# ESP32_Relay_Mainboard.net
KiCad netlist of a schematic drawn in EAGLE
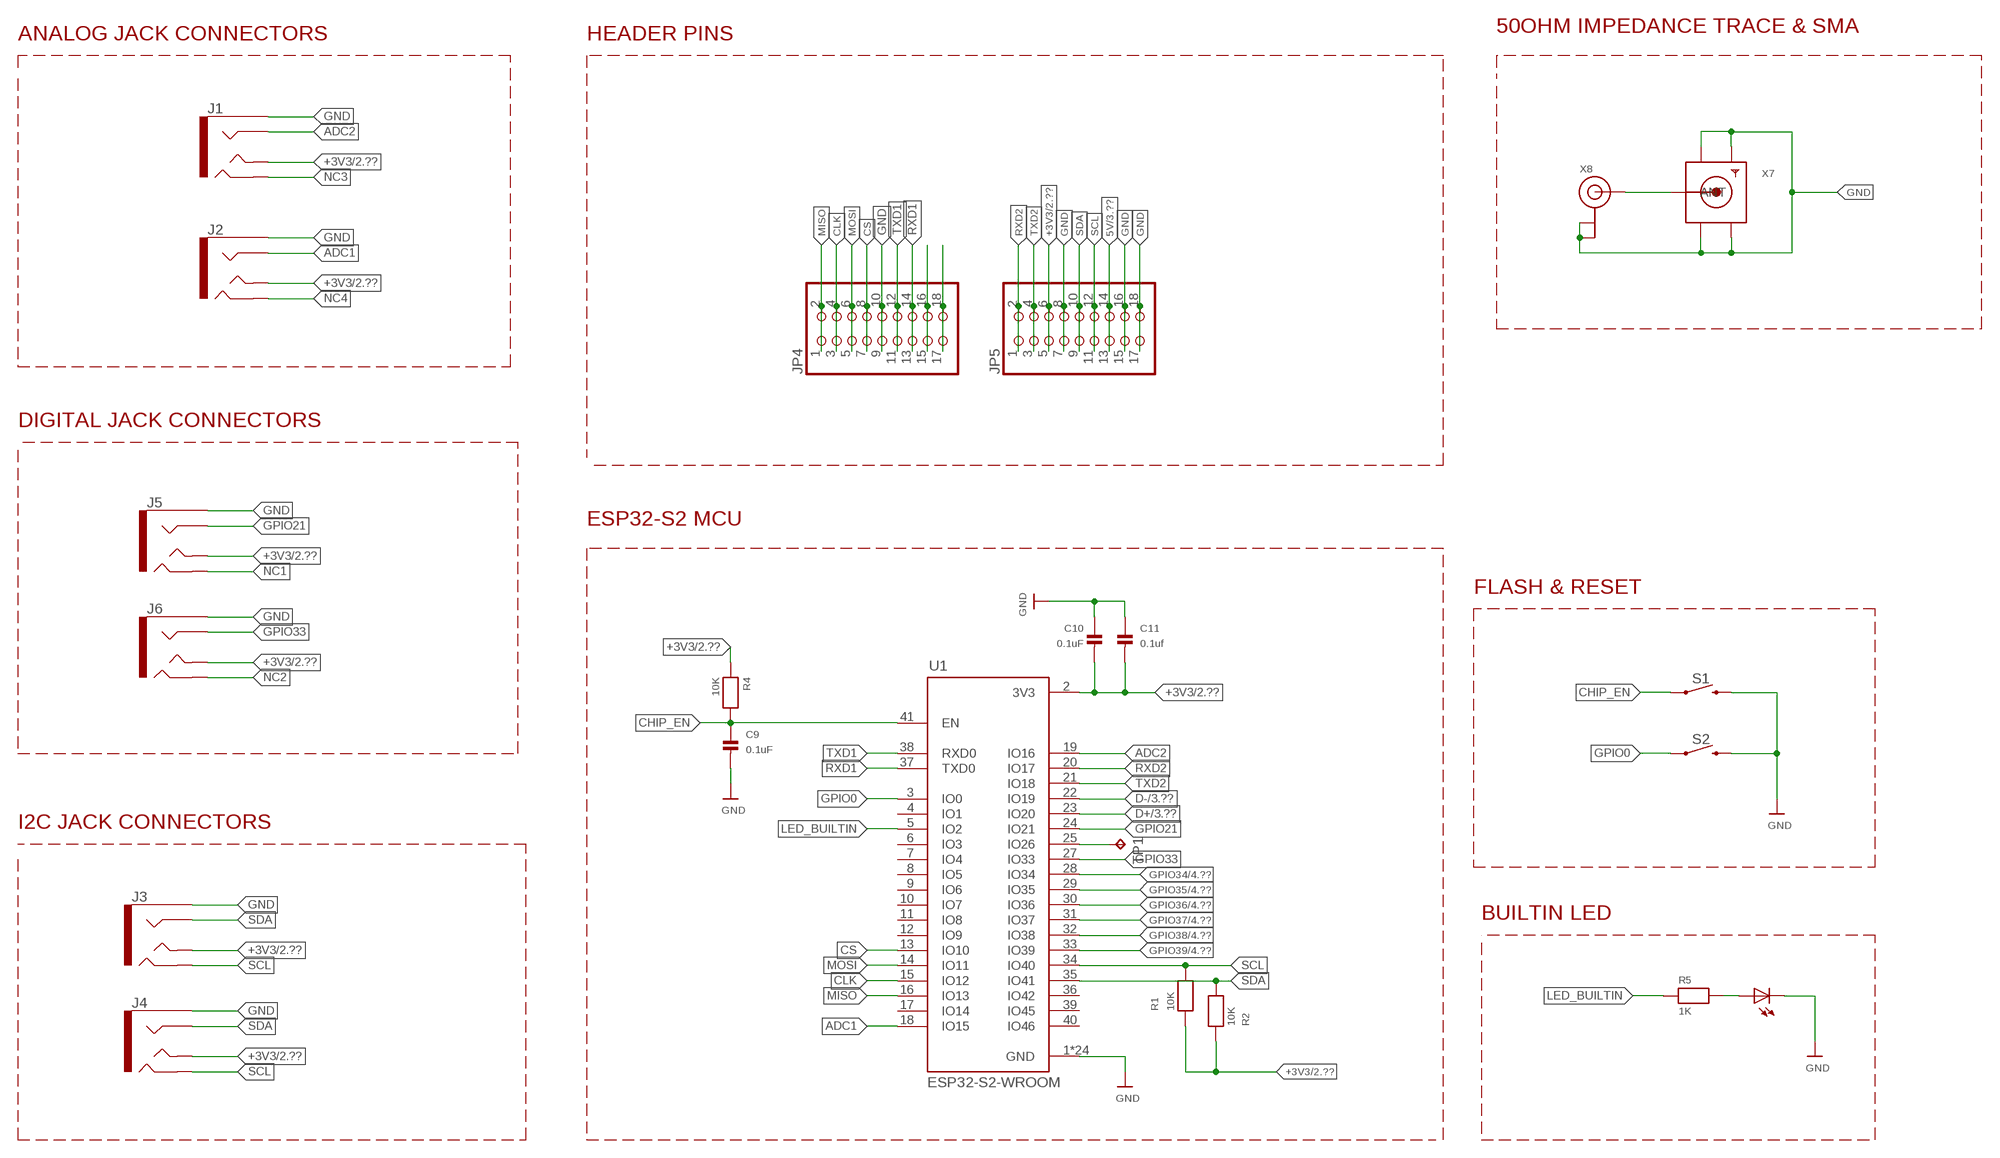
[diagram p0: schematic, sheet 1]
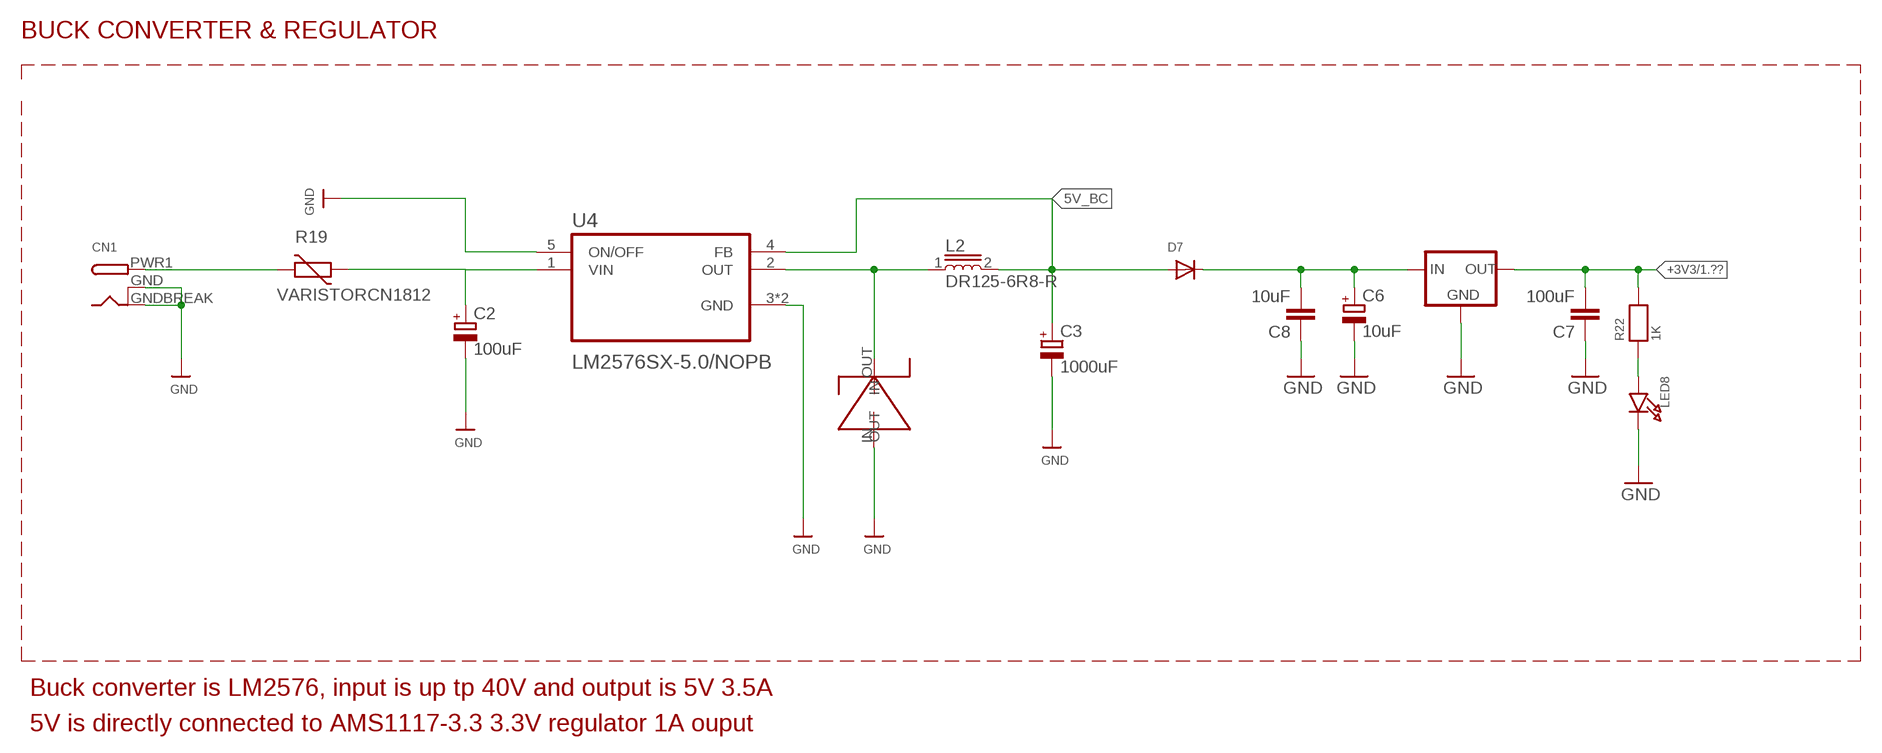
[diagram p1: schematic, sheet 2]
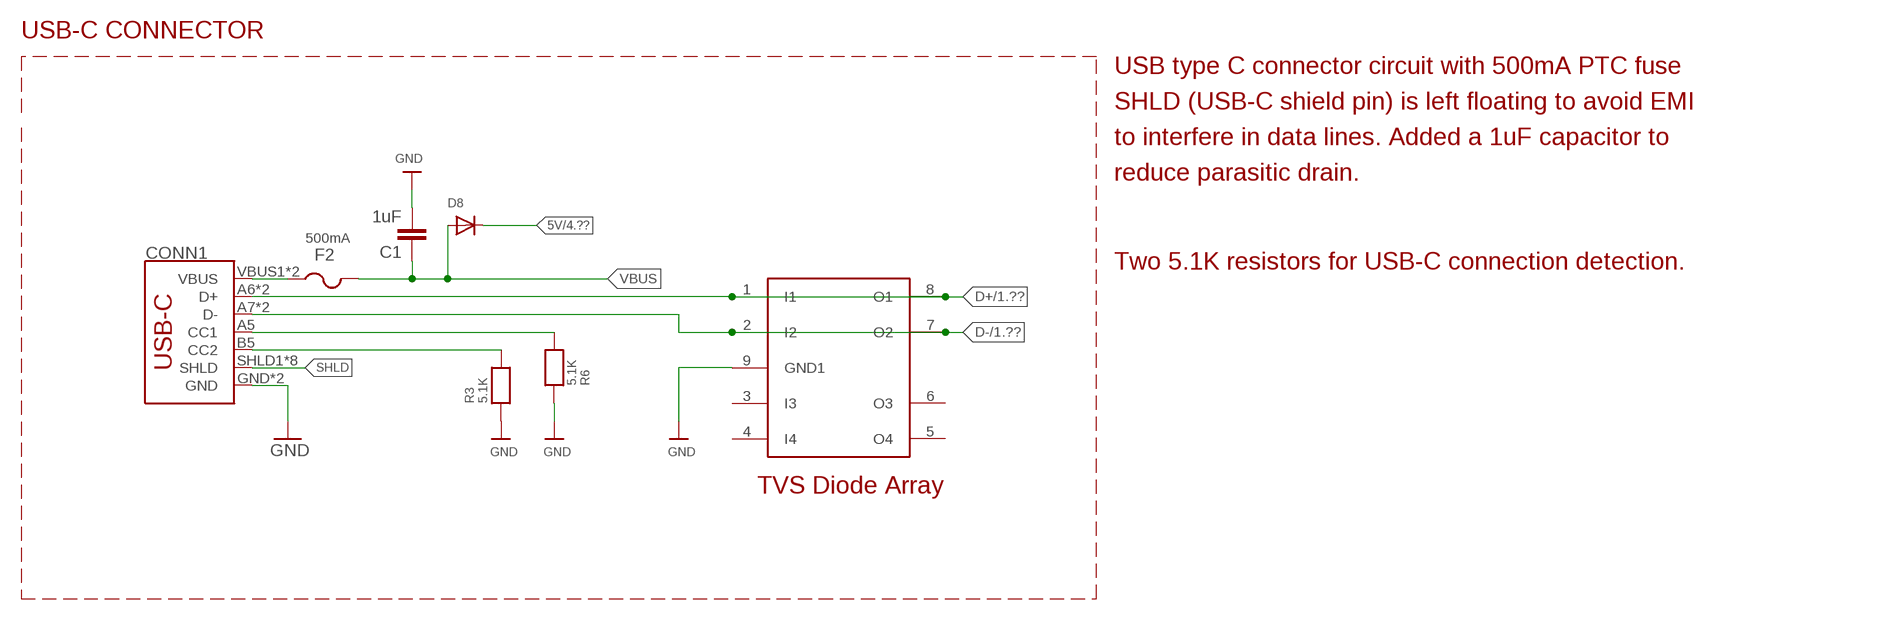
[diagram p2: schematic, sheet 3]
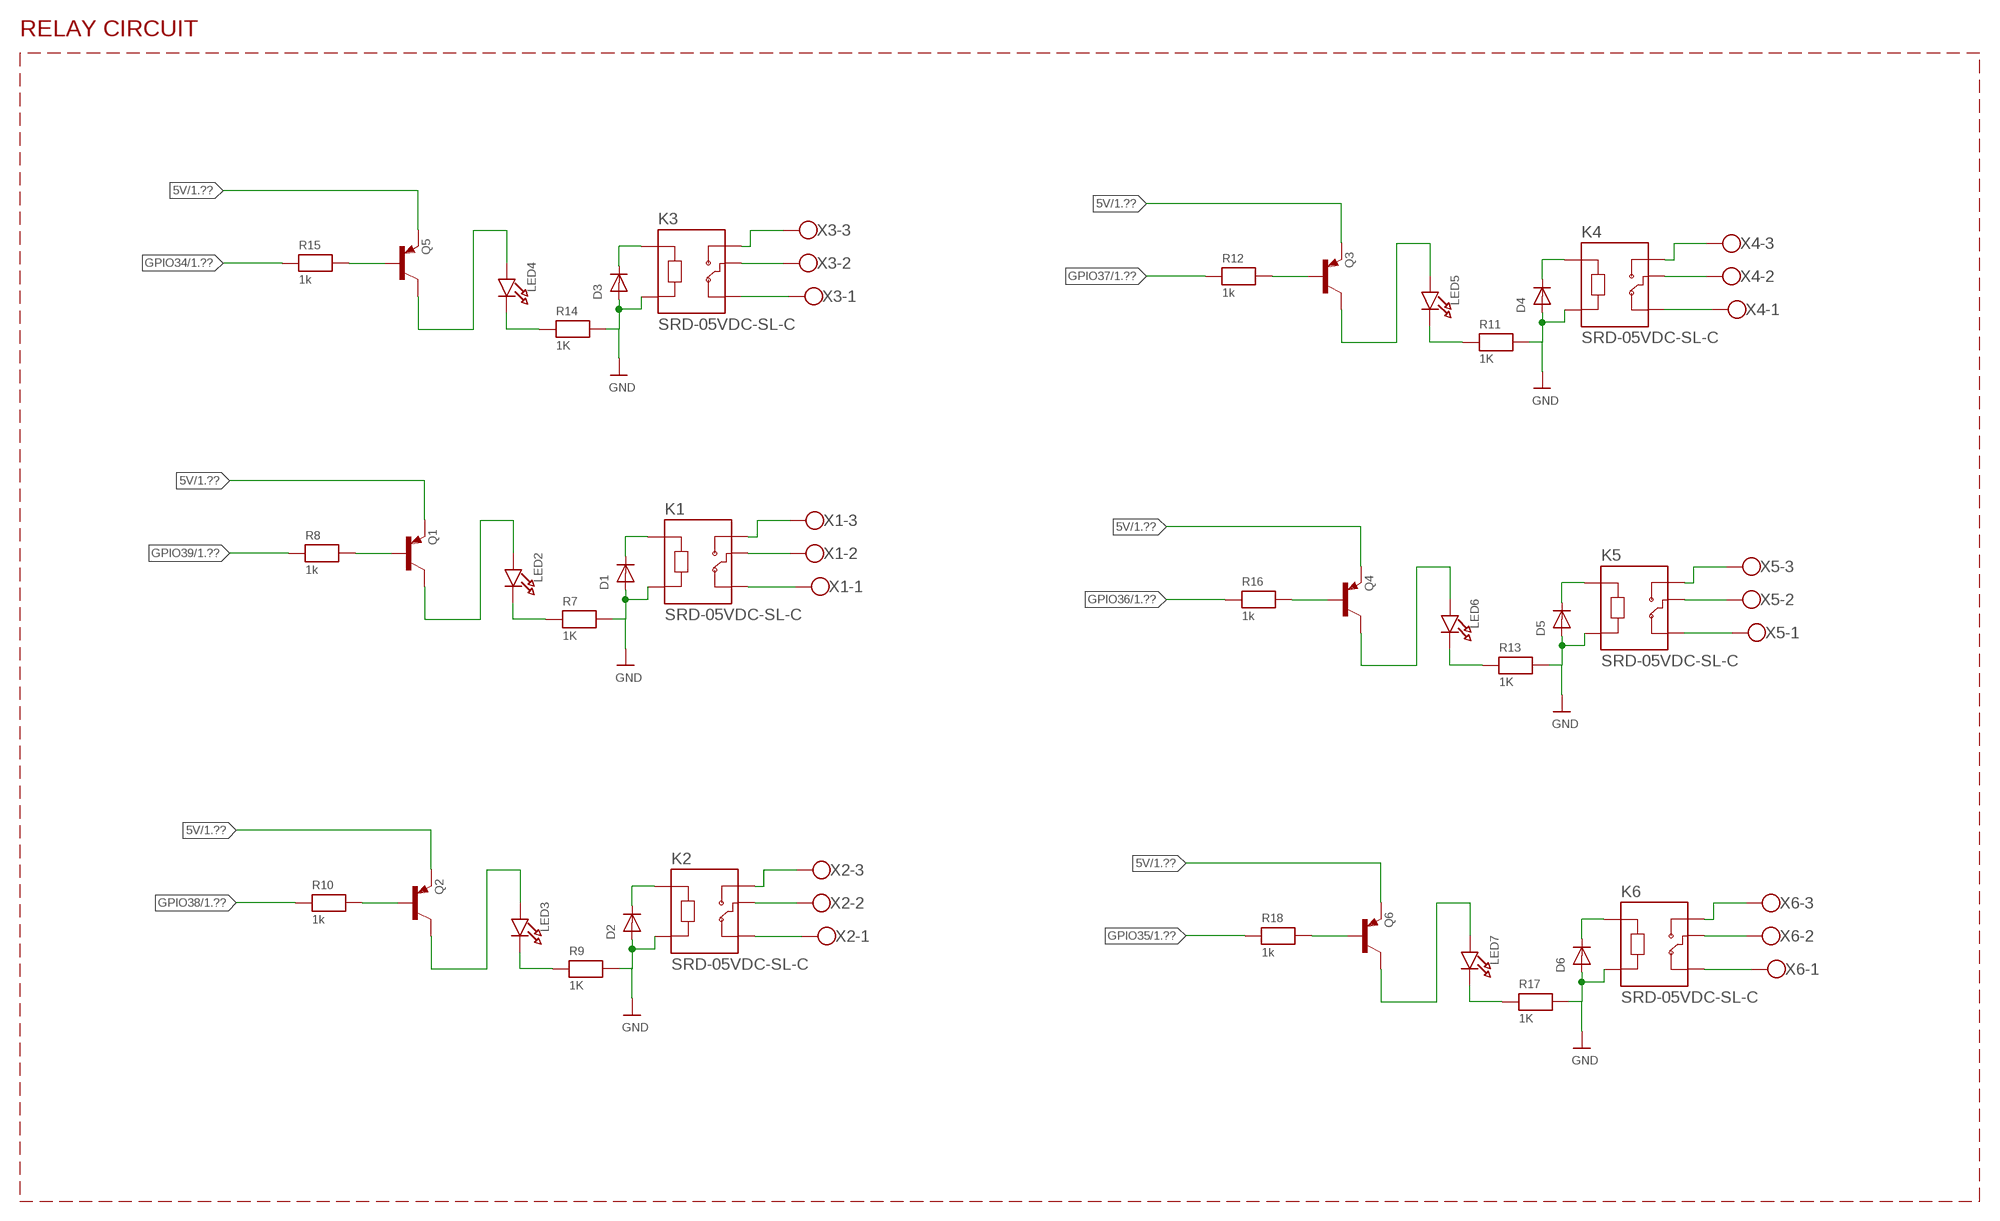
[diagram p3: schematic, sheet 4]

(export (version "E")
  (design (tool "Eeschema 10.0.6"))
  (components
    (comp (ref "C1")
      (value "1uF")
      (footprint "eagle-import:0805")
      (libsource (lib "eagle-import") (part "22UF-0805-6.3V-20%"))
    )
    (comp (ref "CONN1")
      (value "USB_C16PIN")
      (footprint "eagle-import:USB-C-16P")
      (libsource (lib "eagle-import") (part "USB_C16PIN"))
    )
    (comp (ref "D8")
      (value "DIODESOD-123")
      (footprint "eagle-import:SOD-123")
      (libsource (lib "eagle-import") (part "DIODESOD-123"))
    )
    (comp (ref "F2")
      (value "PTCFUSE-1206")
      (footprint "eagle-import:R1206")
      (libsource (lib "eagle-import") (part "PTCFUSE-1206"))
    )
    (comp (ref "R3")
      (value "5.1K")
      (footprint "eagle-import:0603")
      (libsource (lib "eagle-import") (part "RESISTOR0603"))
    )
    (comp (ref "R6")
      (value "5.1K")
      (footprint "eagle-import:0603")
      (libsource (lib "eagle-import") (part "RESISTOR0603"))
    )
    (comp (ref "U$16")
      (value "AZ1045")
      (footprint "eagle-import:RCLAMP0524JTCT")
      (libsource (lib "eagle-import") (part "AZ1045"))
    )
    (comp (ref "D1")
      (value "DIODESMA")
      (footprint "eagle-import:SMADIODE")
      (libsource (lib "eagle-import") (part "DIODESMA"))
    )
    (comp (ref "D2")
      (value "DIODESMA")
      (footprint "eagle-import:SMADIODE")
      (libsource (lib "eagle-import") (part "DIODESMA"))
    )
    (comp (ref "D3")
      (value "DIODESMA")
      (footprint "eagle-import:SMADIODE")
      (libsource (lib "eagle-import") (part "DIODESMA"))
    )
    (comp (ref "D4")
      (value "DIODESMA")
      (footprint "eagle-import:SMADIODE")
      (libsource (lib "eagle-import") (part "DIODESMA"))
    )
    (comp (ref "D5")
      (value "DIODESMA")
      (footprint "eagle-import:SMADIODE")
      (libsource (lib "eagle-import") (part "DIODESMA"))
    )
    (comp (ref "D6")
      (value "DIODESMA")
      (footprint "eagle-import:SMADIODE")
      (libsource (lib "eagle-import") (part "DIODESMA"))
    )
    (comp (ref "K1")
      (value "SRD-05VDC-SL-C")
      (footprint "eagle-import:RELAY_SRD-05VDC-SL-C")
      (fields (field (name "MF") "Songle Relay"))
      (libsource (lib "eagle-import") (part "SRD-05VDC-SL-C"))
    )
    (comp (ref "K2")
      (value "SRD-05VDC-SL-C")
      (footprint "eagle-import:RELAY_SRD-05VDC-SL-C")
      (fields (field (name "MF") "Songle Relay"))
      (libsource (lib "eagle-import") (part "SRD-05VDC-SL-C"))
    )
    (comp (ref "K3")
      (value "SRD-05VDC-SL-C")
      (footprint "eagle-import:RELAY_SRD-05VDC-SL-C")
      (fields (field (name "MF") "Songle Relay"))
      (libsource (lib "eagle-import") (part "SRD-05VDC-SL-C"))
    )
    (comp (ref "K4")
      (value "SRD-05VDC-SL-C")
      (footprint "eagle-import:RELAY_SRD-05VDC-SL-C")
      (fields (field (name "MF") "Songle Relay"))
      (libsource (lib "eagle-import") (part "SRD-05VDC-SL-C"))
    )
    (comp (ref "K5")
      (value "SRD-05VDC-SL-C")
      (footprint "eagle-import:RELAY_SRD-05VDC-SL-C")
      (fields (field (name "MF") "Songle Relay"))
      (libsource (lib "eagle-import") (part "SRD-05VDC-SL-C"))
    )
    (comp (ref "K6")
      (value "SRD-05VDC-SL-C")
      (footprint "eagle-import:RELAY_SRD-05VDC-SL-C")
      (fields (field (name "MF") "Songle Relay"))
      (libsource (lib "eagle-import") (part "SRD-05VDC-SL-C"))
    )
    (comp (ref "LED2")
      (value "LED0805")
      (footprint "eagle-import:CHIPLED_0805")
      (libsource (lib "eagle-import") (part "LED0805"))
    )
    (comp (ref "LED3")
      (value "LED0805")
      (footprint "eagle-import:CHIPLED_0805")
      (libsource (lib "eagle-import") (part "LED0805"))
    )
    (comp (ref "LED4")
      (value "LED0805")
      (footprint "eagle-import:CHIPLED_0805")
      (libsource (lib "eagle-import") (part "LED0805"))
    )
    (comp (ref "LED5")
      (value "LED0805")
      (footprint "eagle-import:CHIPLED_0805")
      (libsource (lib "eagle-import") (part "LED0805"))
    )
    (comp (ref "LED6")
      (value "LED0805")
      (footprint "eagle-import:CHIPLED_0805")
      (libsource (lib "eagle-import") (part "LED0805"))
    )
    (comp (ref "LED7")
      (value "LED0805")
      (footprint "eagle-import:CHIPLED_0805")
      (libsource (lib "eagle-import") (part "LED0805"))
    )
    (comp (ref "Q1")
      (value "-PNP-SOT23-BCE")
      (footprint "eagle-import:SOT23-BCE")
      (libsource (lib "eagle-import") (part "-PNP-SOT23-BCE"))
    )
    (comp (ref "Q2")
      (value "-PNP-SOT23-BCE")
      (footprint "eagle-import:SOT23-BCE")
      (libsource (lib "eagle-import") (part "-PNP-SOT23-BCE"))
    )
    (comp (ref "Q3")
      (value "-PNP-SOT23-BCE")
      (footprint "eagle-import:SOT23-BCE")
      (libsource (lib "eagle-import") (part "-PNP-SOT23-BCE"))
    )
    (comp (ref "Q4")
      (value "-PNP-SOT23-BCE")
      (footprint "eagle-import:SOT23-BCE")
      (libsource (lib "eagle-import") (part "-PNP-SOT23-BCE"))
    )
    (comp (ref "Q5")
      (value "-PNP-SOT23-BCE")
      (footprint "eagle-import:SOT23-BCE")
      (libsource (lib "eagle-import") (part "-PNP-SOT23-BCE"))
    )
    (comp (ref "Q6")
      (value "-PNP-SOT23-BCE")
      (footprint "eagle-import:SOT23-BCE")
      (libsource (lib "eagle-import") (part "-PNP-SOT23-BCE"))
    )
    (comp (ref "R7")
      (value "1K")
      (footprint "eagle-import:0805")
      (libsource (lib "eagle-import") (part "RESISTOR0805"))
    )
    (comp (ref "R8")
      (value "1k")
      (footprint "eagle-import:0805")
      (libsource (lib "eagle-import") (part "RESISTOR0805"))
    )
    (comp (ref "R9")
      (value "1K")
      (footprint "eagle-import:0805")
      (libsource (lib "eagle-import") (part "RESISTOR0805"))
    )
    (comp (ref "R10")
      (value "1k")
      (footprint "eagle-import:0805")
      (libsource (lib "eagle-import") (part "RESISTOR0805"))
    )
    (comp (ref "R11")
      (value "1K")
      (footprint "eagle-import:0805")
      (libsource (lib "eagle-import") (part "RESISTOR0805"))
    )
    (comp (ref "R12")
      (value "1k")
      (footprint "eagle-import:0805")
      (libsource (lib "eagle-import") (part "RESISTOR0805"))
    )
    (comp (ref "R13")
      (value "1K")
      (footprint "eagle-import:0805")
      (libsource (lib "eagle-import") (part "RESISTOR0805"))
    )
    (comp (ref "R14")
      (value "1K")
      (footprint "eagle-import:0805")
      (libsource (lib "eagle-import") (part "RESISTOR0805"))
    )
    (comp (ref "R15")
      (value "1k")
      (footprint "eagle-import:0805")
      (libsource (lib "eagle-import") (part "RESISTOR0805"))
    )
    (comp (ref "R16")
      (value "1k")
      (footprint "eagle-import:0805")
      (libsource (lib "eagle-import") (part "RESISTOR0805"))
    )
    (comp (ref "R17")
      (value "1K")
      (footprint "eagle-import:0805")
      (libsource (lib "eagle-import") (part "RESISTOR0805"))
    )
    (comp (ref "R18")
      (value "1k")
      (footprint "eagle-import:0805")
      (libsource (lib "eagle-import") (part "RESISTOR0805"))
    )
    (comp (ref "X1")
      (value "W237-103")
      (footprint "eagle-import:W237-103")
      (fields (field (name "MPN") "237-103"))
      (libsource (lib "eagle-import") (part "W237-103"))
    )
    (comp (ref "X2")
      (value "W237-103")
      (footprint "eagle-import:W237-103")
      (fields (field (name "MPN") "237-103"))
      (libsource (lib "eagle-import") (part "W237-103"))
    )
    (comp (ref "X3")
      (value "W237-103")
      (footprint "eagle-import:W237-103")
      (fields (field (name "MPN") "237-103"))
      (libsource (lib "eagle-import") (part "W237-103"))
    )
    (comp (ref "X4")
      (value "W237-103")
      (footprint "eagle-import:W237-103")
      (fields (field (name "MPN") "237-103"))
      (libsource (lib "eagle-import") (part "W237-103"))
    )
    (comp (ref "X5")
      (value "W237-103")
      (footprint "eagle-import:W237-103")
      (fields (field (name "MPN") "237-103"))
      (libsource (lib "eagle-import") (part "W237-103"))
    )
    (comp (ref "X6")
      (value "W237-103")
      (footprint "eagle-import:W237-103")
      (fields (field (name "MPN") "237-103"))
      (libsource (lib "eagle-import") (part "W237-103"))
    )
    (comp (ref "3.3V")
      (value "LM1117")
      (footprint "eagle-import:SOT223")
      (libsource (lib "eagle-import") (part "LM1117"))
    )
    (comp (ref "C2")
      (value "100uF")
      (footprint "eagle-import:UD-8X10_NICHICON")
      (libsource (lib "eagle-import") (part "CPOL-EUUD-8X10"))
    )
    (comp (ref "C3")
      (value "1000uF")
      (footprint "eagle-import:UD-10X10_NICHICON")
      (libsource (lib "eagle-import") (part "CPOL-EUUD-10X10"))
    )
    (comp (ref "C6")
      (value "10uF")
      (footprint "eagle-import:UD-5X5,8_NICHICON")
      (libsource (lib "eagle-import") (part "CPOL-EUUD-5X5,8"))
    )
    (comp (ref "C7")
      (value "100uF")
      (footprint "eagle-import:0805")
      (libsource (lib "eagle-import") (part "22UF-0805-6.3V-20%"))
    )
    (comp (ref "C8")
      (value "10uF")
      (footprint "eagle-import:0805")
      (libsource (lib "eagle-import") (part "22UF-0805-6.3V-20%"))
    )
    (comp (ref "CN1")
      (value "DCBARRELSMT")
      (footprint "eagle-import:DCJACK_2MM_SMT")
      (libsource (lib "eagle-import") (part "DCBARRELSMT"))
    )
    (comp (ref "D7")
      (value "DIODESMA")
      (footprint "eagle-import:SMADIODE")
      (libsource (lib "eagle-import") (part "DIODESMA"))
    )
    (comp (ref "L2")
      (value "DR125-6R8-R")
      (footprint "eagle-import:INDM1250X1250X600")
      (fields (field (name "MF") "Eaton"))
      (libsource (lib "eagle-import") (part "DR125-6R8-R"))
    )
    (comp (ref "LED8")
      (value "LED0805")
      (footprint "eagle-import:CHIPLED_0805")
      (libsource (lib "eagle-import") (part "LED0805"))
    )
    (comp (ref "R19")
      (value "VARISTORCN1812")
      (footprint "eagle-import:CT_CN1812")
      (libsource (lib "eagle-import") (part "VARISTORCN1812"))
    )
    (comp (ref "R22")
      (value "1K")
      (footprint "eagle-import:0805")
      (libsource (lib "eagle-import") (part "RESISTOR0805"))
    )
    (comp (ref "U$8")
      (value "DO-214AB")
      (footprint "eagle-import:DO-214AB")
      (fields (field (name "MF") "Littelfuse Inc."))
      (libsource (lib "eagle-import") (part "DO-214AB"))
    )
    (comp (ref "U4")
      (value "LM2576SX-5.0/NOPB")
      (footprint "eagle-import:VREG_TPS79625KTTR")
      (fields (field (name "MF") "National Semiconductor") (field (name "MP") "LM2576SX50"))
      (libsource (lib "eagle-import") (part "LM2576SX-5.0/NOPB"))
    )
    (comp (ref "C9")
      (value "0.1uF")
      (footprint "eagle-import:0805")
      (libsource (lib "eagle-import") (part "CAP_CERAMIC0805"))
    )
    (comp (ref "C10")
      (value "0.1uF")
      (footprint "eagle-import:0805")
      (libsource (lib "eagle-import") (part "CAP_CERAMIC0805"))
    )
    (comp (ref "C11")
      (value "0.1uf")
      (footprint "eagle-import:0805")
      (libsource (lib "eagle-import") (part "CAP_CERAMIC0805"))
    )
    (comp (ref "J1")
      (value "AUDIO_JACK_TRRSSMD_RA")
      (footprint "eagle-import:AUDIO_JACK_3.5MM_TRRS_SMD_RA")
      (libsource (lib "eagle-import") (part "AUDIO_JACK_TRRSSMD_RA"))
    )
    (comp (ref "J2")
      (value "AUDIO_JACK_TRRSSMD_RA")
      (footprint "eagle-import:AUDIO_JACK_3.5MM_TRRS_SMD_RA")
      (libsource (lib "eagle-import") (part "AUDIO_JACK_TRRSSMD_RA"))
    )
    (comp (ref "J3")
      (value "AUDIO_JACK_TRRSSMD_RA")
      (footprint "eagle-import:AUDIO_JACK_3.5MM_TRRS_SMD_RA")
      (libsource (lib "eagle-import") (part "AUDIO_JACK_TRRSSMD_RA"))
    )
    (comp (ref "J4")
      (value "AUDIO_JACK_TRRSSMD_RA")
      (footprint "eagle-import:AUDIO_JACK_3.5MM_TRRS_SMD_RA")
      (libsource (lib "eagle-import") (part "AUDIO_JACK_TRRSSMD_RA"))
    )
    (comp (ref "J5")
      (value "AUDIO_JACK_TRRSSMD_RA")
      (footprint "eagle-import:AUDIO_JACK_3.5MM_TRRS_SMD_RA")
      (libsource (lib "eagle-import") (part "AUDIO_JACK_TRRSSMD_RA"))
    )
    (comp (ref "J6")
      (value "AUDIO_JACK_TRRSSMD_RA")
      (footprint "eagle-import:AUDIO_JACK_3.5MM_TRRS_SMD_RA")
      (libsource (lib "eagle-import") (part "AUDIO_JACK_TRRSSMD_RA"))
    )
    (comp (ref "JP4")
      (value "PINHD-2X9-BIG")
      (footprint "eagle-import:2X09-BIG")
      (libsource (lib "eagle-import") (part "PINHD-2X9-BIG"))
    )
    (comp (ref "JP5")
      (value "PINHD-2X9-BIG")
      (footprint "eagle-import:2X09-BIG")
      (libsource (lib "eagle-import") (part "PINHD-2X9-BIG"))
    )
    (comp (ref "LED1")
      (value "LEDCHIPLED_0805")
      (footprint "eagle-import:CHIPLED_0805")
      (libsource (lib "eagle-import") (part "LEDCHIPLED_0805"))
    )
    (comp (ref "R1")
      (value "10K")
      (footprint "eagle-import:0805")
      (libsource (lib "eagle-import") (part "RESISTOR0805"))
    )
    (comp (ref "R2")
      (value "10K")
      (footprint "eagle-import:0805")
      (libsource (lib "eagle-import") (part "RESISTOR0805"))
    )
    (comp (ref "R4")
      (value "10K")
      (footprint "eagle-import:0805")
      (libsource (lib "eagle-import") (part "RESISTOR0805"))
    )
    (comp (ref "R5")
      (value "1K")
      (footprint "eagle-import:0805")
      (libsource (lib "eagle-import") (part "RESISTOR0805"))
    )
    (comp (ref "S1")
      (value "MOMENTARY-SWITCH-SPST-SMD-5.2-REDUNDANT")
      (footprint "eagle-import:TACTILE_SWITCH_SMD_5.2MM")
      (libsource (lib "eagle-import") (part "MOMENTARY-SWITCH-SPST-SMD-5.2-REDUNDANT"))
    )
    (comp (ref "S2")
      (value "MOMENTARY-SWITCH-SPST-SMD-5.2-REDUNDANT")
      (footprint "eagle-import:TACTILE_SWITCH_SMD_5.2MM")
      (libsource (lib "eagle-import") (part "MOMENTARY-SWITCH-SPST-SMD-5.2-REDUNDANT"))
    )
    (comp (ref "TP1")
      (value "TPTP20R")
      (footprint "eagle-import:TP20R")
      (libsource (lib "eagle-import") (part "TPTP20R"))
    )
    (comp (ref "U1")
      (value "ESP32-S2-WROOM")
      (footprint "eagle-import:XCVR_ESP32-S2-WROOM")
      (fields (field (name "MF") "Espressif Systems"))
      (libsource (lib "eagle-import") (part "ESP32-S2-WROOM"))
    )
    (comp (ref "X7")
      (value "SMACONNECTOR_EDGE")
      (footprint "eagle-import:SMA_EDGELAUNCH")
      (libsource (lib "eagle-import") (part "SMACONNECTOR_EDGE"))
    )
    (comp (ref "X8")
      (value "ANTENNA_U.FL")
      (footprint "eagle-import:U.FL")
      (libsource (lib "eagle-import") (part "ANTENNA_U.FL"))
    )
  )
  (nets
    (net (code "1") (name "+3V3") (class "Default")
      (node (ref "3.3V") (pin "2") (pinfunction "OUT_2") (pintype "passive"))
      (node (ref "C10") (pin "2") (pinfunction "P$2_2") (pintype "passive"))
      (node (ref "C11") (pin "2") (pinfunction "P$2_2") (pintype "passive"))
      (node (ref "C7") (pin "2") (pinfunction "2_2") (pintype "passive"))
      (node (ref "J1") (pin "TIP") (pinfunction "TIP_TIP") (pintype "bidirectional"))
      (node (ref "J2") (pin "TIP") (pinfunction "TIP_TIP") (pintype "bidirectional"))
      (node (ref "J3") (pin "TIP") (pinfunction "TIP_TIP") (pintype "bidirectional"))
      (node (ref "J4") (pin "TIP") (pinfunction "TIP_TIP") (pintype "bidirectional"))
      (node (ref "J5") (pin "TIP") (pinfunction "TIP_TIP") (pintype "bidirectional"))
      (node (ref "J6") (pin "TIP") (pinfunction "TIP_TIP") (pintype "bidirectional"))
      (node (ref "JP5") (pin "5") (pinfunction "5_5") (pintype "passive"))
      (node (ref "JP5") (pin "6") (pinfunction "6_6") (pintype "passive"))
      (node (ref "R1") (pin "1") (pinfunction "1_1") (pintype "passive"))
      (node (ref "R2") (pin "1") (pinfunction "1_1") (pintype "passive"))
      (node (ref "R22") (pin "2") (pinfunction "2_2") (pintype "passive"))
      (node (ref "R4") (pin "1") (pinfunction "1_1") (pintype "passive"))
      (node (ref "U1") (pin "2") (pinfunction "3V3_2") (pintype "power_in"))
    )
    (net (code "2") (name "5V") (class "Default")
      (node (ref "3.3V") (pin "3") (pinfunction "IN_3") (pintype "input"))
      (node (ref "C6") (pin "+") (pinfunction "+_+") (pintype "passive"))
      (node (ref "C8") (pin "2") (pinfunction "2_2") (pintype "passive"))
      (node (ref "D7") (pin "C") (pinfunction "C_C") (pintype "passive"))
      (node (ref "D8") (pin "C") (pinfunction "C_C") (pintype "passive"))
      (node (ref "JP5") (pin "13") (pinfunction "13_13") (pintype "passive"))
      (node (ref "JP5") (pin "14") (pinfunction "14_14") (pintype "passive"))
      (node (ref "Q1") (pin "E") (pinfunction "E_E") (pintype "passive"))
      (node (ref "Q2") (pin "E") (pinfunction "E_E") (pintype "passive"))
      (node (ref "Q3") (pin "E") (pinfunction "E_E") (pintype "passive"))
      (node (ref "Q4") (pin "E") (pinfunction "E_E") (pintype "passive"))
      (node (ref "Q5") (pin "E") (pinfunction "E_E") (pintype "passive"))
      (node (ref "Q6") (pin "E") (pinfunction "E_E") (pintype "passive"))
    )
    (net (code "3") (name "5V_BC") (class "Default")
      (node (ref "C3") (pin "+") (pinfunction "+_+") (pintype "passive"))
      (node (ref "D7") (pin "A") (pinfunction "A_A") (pintype "passive"))
      (node (ref "L2") (pin "2") (pinfunction "2_2") (pintype "passive"))
      (node (ref "U4") (pin "4") (pinfunction "FB_4") (pintype "output"))
    )
    (net (code "4") (name "ADC1") (class "Default")
      (node (ref "J2") (pin "RING1") (pinfunction "RING1_RING1") (pintype "bidirectional"))
      (node (ref "U1") (pin "18") (pinfunction "IO15_18") (pintype "bidirectional"))
    )
    (net (code "5") (name "ADC2") (class "Default")
      (node (ref "J1") (pin "RING1") (pinfunction "RING1_RING1") (pintype "bidirectional"))
      (node (ref "U1") (pin "19") (pinfunction "IO16_19") (pintype "bidirectional"))
    )
    (net (code "6") (name "CHIP_EN") (class "Default")
      (node (ref "C9") (pin "1") (pinfunction "P$1_1") (pintype "passive"))
      (node (ref "R4") (pin "2") (pinfunction "2_2") (pintype "passive"))
      (node (ref "S1") (pin "1") (pinfunction "1_1") (pintype "passive"))
      (node (ref "S1") (pin "2") (pinfunction "1_2") (pintype "passive"))
      (node (ref "U1") (pin "41") (pinfunction "EN_41") (pintype "input"))
    )
    (net (code "7") (name "CLK") (class "Default")
      (node (ref "JP4") (pin "3") (pinfunction "3_3") (pintype "passive"))
      (node (ref "JP4") (pin "4") (pinfunction "4_4") (pintype "passive"))
      (node (ref "U1") (pin "15") (pinfunction "IO12_15") (pintype "bidirectional"))
    )
    (net (code "8") (name "CS") (class "Default")
      (node (ref "JP4") (pin "7") (pinfunction "7_7") (pintype "passive"))
      (node (ref "JP4") (pin "8") (pinfunction "8_8") (pintype "passive"))
      (node (ref "U1") (pin "13") (pinfunction "IO10_13") (pintype "bidirectional"))
    )
    (net (code "9") (name "D+") (class "Default")
      (node (ref "CONN1") (pin "A6") (pinfunction "D+_A6") (pintype "bidirectional"))
      (node (ref "CONN1") (pin "B6") (pinfunction "D+_B6") (pintype "bidirectional"))
      (node (ref "U$16") (pin "1") (pinfunction "I1_1") (pintype "bidirectional"))
      (node (ref "U$16") (pin "8") (pinfunction "O1_8") (pintype "bidirectional"))
      (node (ref "U1") (pin "23") (pinfunction "IO20_23") (pintype "bidirectional"))
    )
    (net (code "10") (name "D-") (class "Default")
      (node (ref "CONN1") (pin "A7") (pinfunction "D-_A7") (pintype "bidirectional"))
      (node (ref "CONN1") (pin "B7") (pinfunction "D-_B7") (pintype "bidirectional"))
      (node (ref "U$16") (pin "2") (pinfunction "I2_2") (pintype "bidirectional"))
      (node (ref "U$16") (pin "7") (pinfunction "O2_7") (pintype "bidirectional"))
      (node (ref "U1") (pin "22") (pinfunction "IO19_22") (pintype "bidirectional"))
    )
    (net (code "11") (name "GND") (class "Default")
      (node (ref "3.3V") (pin "1") (pinfunction "GND_1") (pintype "input"))
      (node (ref "C1") (pin "2") (pinfunction "2_2") (pintype "passive"))
      (node (ref "C10") (pin "1") (pinfunction "P$1_1") (pintype "passive"))
      (node (ref "C11") (pin "1") (pinfunction "P$1_1") (pintype "passive"))
      (node (ref "C2") (pin "-") (pinfunction "-_-") (pintype "passive"))
      (node (ref "C3") (pin "-") (pinfunction "-_-") (pintype "passive"))
      (node (ref "C6") (pin "-") (pinfunction "-_-") (pintype "passive"))
      (node (ref "C7") (pin "1") (pinfunction "1_1") (pintype "passive"))
      (node (ref "C8") (pin "1") (pinfunction "1_1") (pintype "passive"))
      (node (ref "C9") (pin "2") (pinfunction "P$2_2") (pintype "passive"))
      (node (ref "CN1") (pin "GND") (pinfunction "GNDBREAK_GND") (pintype "power_in"))
      (node (ref "CN1") (pin "GNDBREAK") (pinfunction "GND_GNDBREAK") (pintype "power_in"))
      (node (ref "CONN1") (pin "GND") (pinfunction "GND_GND") (pintype "bidirectional"))
      (node (ref "CONN1") (pin "GND2") (pinfunction "GND_GND2") (pintype "bidirectional"))
      (node (ref "D1") (pin "A") (pinfunction "A_A") (pintype "passive"))
      (node (ref "D2") (pin "A") (pinfunction "A_A") (pintype "passive"))
      (node (ref "D3") (pin "A") (pinfunction "A_A") (pintype "passive"))
      (node (ref "D4") (pin "A") (pinfunction "A_A") (pintype "passive"))
      (node (ref "D5") (pin "A") (pinfunction "A_A") (pintype "passive"))
      (node (ref "D6") (pin "A") (pinfunction "A_A") (pintype "passive"))
      (node (ref "J1") (pin "EARTH") (pinfunction "EARTH_EARTH") (pintype "bidirectional"))
      (node (ref "J2") (pin "EARTH") (pinfunction "EARTH_EARTH") (pintype "bidirectional"))
      (node (ref "J3") (pin "EARTH") (pinfunction "EARTH_EARTH") (pintype "bidirectional"))
      (node (ref "J4") (pin "EARTH") (pinfunction "EARTH_EARTH") (pintype "bidirectional"))
      (node (ref "J5") (pin "EARTH") (pinfunction "EARTH_EARTH") (pintype "bidirectional"))
      (node (ref "J6") (pin "EARTH") (pinfunction "EARTH_EARTH") (pintype "bidirectional"))
      (node (ref "JP4") (pin "10") (pinfunction "10_10") (pintype "passive"))
      (node (ref "JP4") (pin "9") (pinfunction "9_9") (pintype "passive"))
      (node (ref "JP5") (pin "15") (pinfunction "15_15") (pintype "passive"))
      (node (ref "JP5") (pin "16") (pinfunction "16_16") (pintype "passive"))
      (node (ref "JP5") (pin "17") (pinfunction "17_17") (pintype "passive"))
      (node (ref "JP5") (pin "18") (pinfunction "18_18") (pintype "passive"))
      (node (ref "JP5") (pin "7") (pinfunction "7_7") (pintype "passive"))
      (node (ref "JP5") (pin "8") (pinfunction "8_8") (pintype "passive"))
      (node (ref "K1") (pin "A2") (pinfunction "A2_A2") (pintype "passive"))
      (node (ref "K2") (pin "A2") (pinfunction "A2_A2") (pintype "passive"))
      (node (ref "K3") (pin "A2") (pinfunction "A2_A2") (pintype "passive"))
      (node (ref "K4") (pin "A2") (pinfunction "A2_A2") (pintype "passive"))
      (node (ref "K5") (pin "A2") (pinfunction "A2_A2") (pintype "passive"))
      (node (ref "K6") (pin "A2") (pinfunction "A2_A2") (pintype "passive"))
      (node (ref "LED1") (pin "C") (pinfunction "C_C") (pintype "passive"))
      (node (ref "LED8") (pin "C") (pinfunction "C_C") (pintype "passive"))
      (node (ref "R11") (pin "2") (pinfunction "2_2") (pintype "passive"))
      (node (ref "R13") (pin "2") (pinfunction "2_2") (pintype "passive"))
      (node (ref "R14") (pin "2") (pinfunction "2_2") (pintype "passive"))
      (node (ref "R17") (pin "2") (pinfunction "2_2") (pintype "passive"))
      (node (ref "R3") (pin "1") (pinfunction "1_1") (pintype "passive"))
      (node (ref "R6") (pin "1") (pinfunction "1_1") (pintype "passive"))
      (node (ref "R7") (pin "2") (pinfunction "2_2") (pintype "passive"))
      (node (ref "R9") (pin "2") (pinfunction "2_2") (pintype "passive"))
      (node (ref "S1") (pin "3") (pinfunction "2_3") (pintype "passive"))
      (node (ref "S1") (pin "4") (pinfunction "2_4") (pintype "passive"))
      (node (ref "S2") (pin "3") (pinfunction "2_3") (pintype "passive"))
      (node (ref "S2") (pin "4") (pinfunction "2_4") (pintype "passive"))
      (node (ref "U$16") (pin "9") (pinfunction "GND1_9") (pintype "bidirectional"))
      (node (ref "U$8") (pin "IN") (pinfunction "IN_IN") (pintype "bidirectional"))
      (node (ref "U1") (pin "1") (pinfunction "GND_1") (pintype "power_in"))
      (node (ref "U1") (pin "26") (pinfunction "GND_26") (pintype "power_in"))
      (node (ref "U1") (pin "42") (pinfunction "GND_42") (pintype "power_in"))
      (node (ref "U1") (pin "43.1") (pinfunction "GND_43.1") (pintype "power_in"))
      (node (ref "U1") (pin "43.10") (pinfunction "GND_43.10") (pintype "power_in"))
      (node (ref "U1") (pin "43.11") (pinfunction "GND_43.11") (pintype "power_in"))
      (node (ref "U1") (pin "43.12") (pinfunction "GND_43.12") (pintype "power_in"))
      (node (ref "U1") (pin "43.13") (pinfunction "GND_43.13") (pintype "power_in"))
      (node (ref "U1") (pin "43.14") (pinfunction "GND_43.14") (pintype "power_in"))
      (node (ref "U1") (pin "43.15") (pinfunction "GND_43.15") (pintype "power_in"))
      (node (ref "U1") (pin "43.16") (pinfunction "GND_43.16") (pintype "power_in"))
      (node (ref "U1") (pin "43.17") (pinfunction "GND_43.17") (pintype "power_in"))
      (node (ref "U1") (pin "43.18") (pinfunction "GND_43.18") (pintype "power_in"))
      (node (ref "U1") (pin "43.19") (pinfunction "GND_43.19") (pintype "power_in"))
      (node (ref "U1") (pin "43.2") (pinfunction "GND_43.2") (pintype "power_in"))
      (node (ref "U1") (pin "43.20") (pinfunction "GND_43.20") (pintype "power_in"))
      (node (ref "U1") (pin "43.21") (pinfunction "GND_43.21") (pintype "power_in"))
      (node (ref "U1") (pin "43.3") (pinfunction "GND_43.3") (pintype "power_in"))
      (node (ref "U1") (pin "43.4") (pinfunction "GND_43.4") (pintype "power_in"))
      (node (ref "U1") (pin "43.5") (pinfunction "GND_43.5") (pintype "power_in"))
      (node (ref "U1") (pin "43.6") (pinfunction "GND_43.6") (pintype "power_in"))
      (node (ref "U1") (pin "43.7") (pinfunction "GND_43.7") (pintype "power_in"))
      (node (ref "U1") (pin "43.8") (pinfunction "GND_43.8") (pintype "power_in"))
      (node (ref "U1") (pin "43.9") (pinfunction "GND_43.9") (pintype "power_in"))
      (node (ref "U4") (pin "3") (pinfunction "GND_3") (pintype "power_in"))
      (node (ref "U4") (pin "5") (pinfunction "ON/OFF_5") (pintype "input"))
      (node (ref "U4") (pin "6") (pinfunction "GND_6") (pintype "power_in"))
      (node (ref "X7") (pin "GND@1") (pinfunction "GND4_GND@1") (pintype "power_in"))
      (node (ref "X7") (pin "GND@2") (pinfunction "GND3_GND@2") (pintype "power_in"))
      (node (ref "X7") (pin "GND@3") (pinfunction "GND2_GND@3") (pintype "power_in"))
      (node (ref "X7") (pin "GND@4") (pinfunction "GND1_GND@4") (pintype "power_in"))
      (node (ref "X8") (pin "1") (pinfunction "GND_1") (pintype "passive"))
      (node (ref "X8") (pin "2") (pinfunction "GND_2") (pintype "passive"))
    )
    (net (code "12") (name "GPIO0") (class "Default")
      (node (ref "S2") (pin "1") (pinfunction "1_1") (pintype "passive"))
      (node (ref "S2") (pin "2") (pinfunction "1_2") (pintype "passive"))
      (node (ref "U1") (pin "3") (pinfunction "IO0_3") (pintype "bidirectional"))
    )
    (net (code "13") (name "GPIO21") (class "Default")
      (node (ref "J5") (pin "RING1") (pinfunction "RING1_RING1") (pintype "bidirectional"))
      (node (ref "U1") (pin "24") (pinfunction "IO21_24") (pintype "bidirectional"))
    )
    (net (code "14") (name "GPIO33") (class "Default")
      (node (ref "J6") (pin "RING1") (pinfunction "RING1_RING1") (pintype "bidirectional"))
      (node (ref "U1") (pin "27") (pinfunction "IO33_27") (pintype "bidirectional"))
    )
    (net (code "15") (name "GPIO34") (class "Default")
      (node (ref "R15") (pin "1") (pinfunction "1_1") (pintype "passive"))
      (node (ref "U1") (pin "28") (pinfunction "IO34_28") (pintype "bidirectional"))
    )
    (net (code "16") (name "GPIO35") (class "Default")
      (node (ref "R18") (pin "1") (pinfunction "1_1") (pintype "passive"))
      (node (ref "U1") (pin "29") (pinfunction "IO35_29") (pintype "bidirectional"))
    )
    (net (code "17") (name "GPIO36") (class "Default")
      (node (ref "R16") (pin "1") (pinfunction "1_1") (pintype "passive"))
      (node (ref "U1") (pin "30") (pinfunction "IO36_30") (pintype "bidirectional"))
    )
    (net (code "18") (name "GPIO37") (class "Default")
      (node (ref "R12") (pin "1") (pinfunction "1_1") (pintype "passive"))
      (node (ref "U1") (pin "31") (pinfunction "IO37_31") (pintype "bidirectional"))
    )
    (net (code "19") (name "GPIO38") (class "Default")
      (node (ref "R10") (pin "1") (pinfunction "1_1") (pintype "passive"))
      (node (ref "U1") (pin "32") (pinfunction "IO38_32") (pintype "bidirectional"))
    )
    (net (code "20") (name "GPIO39") (class "Default")
      (node (ref "R8") (pin "1") (pinfunction "1_1") (pintype "passive"))
      (node (ref "U1") (pin "33") (pinfunction "IO39_33") (pintype "bidirectional"))
    )
    (net (code "21") (name "LED_BUILTIN") (class "Default")
      (node (ref "R5") (pin "1") (pinfunction "1_1") (pintype "passive"))
      (node (ref "U1") (pin "5") (pinfunction "IO2_5") (pintype "bidirectional"))
    )
    (net (code "22") (name "MISO") (class "Default")
      (node (ref "JP4") (pin "1") (pinfunction "1_1") (pintype "passive"))
      (node (ref "JP4") (pin "2") (pinfunction "2_2") (pintype "passive"))
      (node (ref "U1") (pin "16") (pinfunction "IO13_16") (pintype "bidirectional"))
    )
    (net (code "23") (name "MOSI") (class "Default")
      (node (ref "JP4") (pin "5") (pinfunction "5_5") (pintype "passive"))
      (node (ref "JP4") (pin "6") (pinfunction "6_6") (pintype "passive"))
      (node (ref "U1") (pin "14") (pinfunction "IO11_14") (pintype "bidirectional"))
    )
    (net (code "24") (name "NC1") (class "Default")
      (node (ref "J5") (pin "RING2") (pinfunction "RING2_RING2") (pintype "bidirectional"))
    )
    (net (code "25") (name "NC2") (class "Default")
      (node (ref "J6") (pin "RING2") (pinfunction "RING2_RING2") (pintype "bidirectional"))
    )
    (net (code "26") (name "NC3") (class "Default")
      (node (ref "J1") (pin "RING2") (pinfunction "RING2_RING2") (pintype "bidirectional"))
    )
    (net (code "27") (name "NC4") (class "Default")
      (node (ref "J2") (pin "RING2") (pinfunction "RING2_RING2") (pintype "bidirectional"))
    )
    (net (code "28") (name "Net-(CN1-PWR)") (class "Default")
      (node (ref "CN1") (pin "PWR1") (pinfunction "PWR_PWR1") (pintype "power_in"))
      (node (ref "R19") (pin "2") (pinfunction "2_2") (pintype "passive"))
    )
    (net (code "29") (name "Net-(CONN1-CC1)") (class "Default")
      (node (ref "CONN1") (pin "A5") (pinfunction "CC1_A5") (pintype "bidirectional"))
      (node (ref "R6") (pin "2") (pinfunction "2_2") (pintype "passive"))
    )
    (net (code "30") (name "Net-(CONN1-CC2)") (class "Default")
      (node (ref "CONN1") (pin "B5") (pinfunction "CC2_B5") (pintype "bidirectional"))
      (node (ref "R3") (pin "2") (pinfunction "2_2") (pintype "passive"))
    )
    (net (code "31") (name "Net-(CONN1-VBUS-PadVBUS1)") (class "Default")
      (node (ref "CONN1") (pin "VBUS1") (pinfunction "VBUS_VBUS1") (pintype "bidirectional"))
      (node (ref "CONN1") (pin "VBUS2") (pinfunction "VBUS_VBUS2") (pintype "bidirectional"))
      (node (ref "F2") (pin "1") (pinfunction "1_1") (pintype "passive"))
    )
    (net (code "32") (name "Net-(D1-PadC)") (class "Default")
      (node (ref "D1") (pin "C") (pinfunction "C_C") (pintype "passive"))
      (node (ref "K1") (pin "A1") (pinfunction "A1_A1") (pintype "passive"))
    )
    (net (code "33") (name "Net-(D2-PadC)") (class "Default")
      (node (ref "D2") (pin "C") (pinfunction "C_C") (pintype "passive"))
      (node (ref "K2") (pin "A1") (pinfunction "A1_A1") (pintype "passive"))
    )
    (net (code "34") (name "Net-(D3-PadC)") (class "Default")
      (node (ref "D3") (pin "C") (pinfunction "C_C") (pintype "passive"))
      (node (ref "K3") (pin "A1") (pinfunction "A1_A1") (pintype "passive"))
    )
    (net (code "35") (name "Net-(D4-PadC)") (class "Default")
      (node (ref "D4") (pin "C") (pinfunction "C_C") (pintype "passive"))
      (node (ref "K4") (pin "A1") (pinfunction "A1_A1") (pintype "passive"))
    )
    (net (code "36") (name "Net-(D5-PadC)") (class "Default")
      (node (ref "D5") (pin "C") (pinfunction "C_C") (pintype "passive"))
      (node (ref "K5") (pin "A1") (pinfunction "A1_A1") (pintype "passive"))
    )
    (net (code "37") (name "Net-(D6-PadC)") (class "Default")
      (node (ref "D6") (pin "C") (pinfunction "C_C") (pintype "passive"))
      (node (ref "K6") (pin "A1") (pinfunction "A1_A1") (pintype "passive"))
    )
    (net (code "38") (name "Net-(JP4-Pad15)") (class "Default")
      (node (ref "JP4") (pin "15") (pinfunction "15_15") (pintype "passive"))
      (node (ref "JP4") (pin "16") (pinfunction "16_16") (pintype "passive"))
    )
    (net (code "39") (name "Net-(JP4-Pad17)") (class "Default")
      (node (ref "JP4") (pin "17") (pinfunction "17_17") (pintype "passive"))
      (node (ref "JP4") (pin "18") (pinfunction "18_18") (pintype "passive"))
    )
    (net (code "40") (name "Net-(LED1-PadA)") (class "Default")
      (node (ref "LED1") (pin "A") (pinfunction "A_A") (pintype "passive"))
      (node (ref "R5") (pin "2") (pinfunction "2_2") (pintype "passive"))
    )
    (net (code "41") (name "Net-(LED2-PadA)") (class "Default")
      (node (ref "LED2") (pin "A") (pinfunction "A_A") (pintype "passive"))
      (node (ref "Q1") (pin "C") (pinfunction "C_C") (pintype "passive"))
    )
    (net (code "42") (name "Net-(LED2-PadC)") (class "Default")
      (node (ref "LED2") (pin "C") (pinfunction "C_C") (pintype "passive"))
      (node (ref "R7") (pin "1") (pinfunction "1_1") (pintype "passive"))
    )
    (net (code "43") (name "Net-(LED3-PadA)") (class "Default")
      (node (ref "LED3") (pin "A") (pinfunction "A_A") (pintype "passive"))
      (node (ref "Q2") (pin "C") (pinfunction "C_C") (pintype "passive"))
    )
    (net (code "44") (name "Net-(LED3-PadC)") (class "Default")
      (node (ref "LED3") (pin "C") (pinfunction "C_C") (pintype "passive"))
      (node (ref "R9") (pin "1") (pinfunction "1_1") (pintype "passive"))
    )
    (net (code "45") (name "Net-(LED4-PadA)") (class "Default")
      (node (ref "LED4") (pin "A") (pinfunction "A_A") (pintype "passive"))
      (node (ref "Q5") (pin "C") (pinfunction "C_C") (pintype "passive"))
    )
    (net (code "46") (name "Net-(LED4-PadC)") (class "Default")
      (node (ref "LED4") (pin "C") (pinfunction "C_C") (pintype "passive"))
      (node (ref "R14") (pin "1") (pinfunction "1_1") (pintype "passive"))
    )
    (net (code "47") (name "Net-(LED5-PadA)") (class "Default")
      (node (ref "LED5") (pin "A") (pinfunction "A_A") (pintype "passive"))
      (node (ref "Q3") (pin "C") (pinfunction "C_C") (pintype "passive"))
    )
    (net (code "48") (name "Net-(LED5-PadC)") (class "Default")
      (node (ref "LED5") (pin "C") (pinfunction "C_C") (pintype "passive"))
      (node (ref "R11") (pin "1") (pinfunction "1_1") (pintype "passive"))
    )
    (net (code "49") (name "Net-(LED6-PadA)") (class "Default")
      (node (ref "LED6") (pin "A") (pinfunction "A_A") (pintype "passive"))
      (node (ref "Q4") (pin "C") (pinfunction "C_C") (pintype "passive"))
    )
    (net (code "50") (name "Net-(LED6-PadC)") (class "Default")
      (node (ref "LED6") (pin "C") (pinfunction "C_C") (pintype "passive"))
      (node (ref "R13") (pin "1") (pinfunction "1_1") (pintype "passive"))
    )
    (net (code "51") (name "Net-(LED7-PadA)") (class "Default")
      (node (ref "LED7") (pin "A") (pinfunction "A_A") (pintype "passive"))
      (node (ref "Q6") (pin "C") (pinfunction "C_C") (pintype "passive"))
    )
    (net (code "52") (name "Net-(LED7-PadC)") (class "Default")
      (node (ref "LED7") (pin "C") (pinfunction "C_C") (pintype "passive"))
      (node (ref "R17") (pin "1") (pinfunction "1_1") (pintype "passive"))
    )
    (net (code "53") (name "Net-(LED8-PadA)") (class "Default")
      (node (ref "LED8") (pin "A") (pinfunction "A_A") (pintype "passive"))
      (node (ref "R22") (pin "1") (pinfunction "1_1") (pintype "passive"))
    )
    (net (code "54") (name "Net-(Q1-PadB)") (class "Default")
      (node (ref "Q1") (pin "B") (pinfunction "B_B") (pintype "passive"))
      (node (ref "R8") (pin "2") (pinfunction "2_2") (pintype "passive"))
    )
    (net (code "55") (name "Net-(Q2-PadB)") (class "Default")
      (node (ref "Q2") (pin "B") (pinfunction "B_B") (pintype "passive"))
      (node (ref "R10") (pin "2") (pinfunction "2_2") (pintype "passive"))
    )
    (net (code "56") (name "Net-(Q3-PadB)") (class "Default")
      (node (ref "Q3") (pin "B") (pinfunction "B_B") (pintype "passive"))
      (node (ref "R12") (pin "2") (pinfunction "2_2") (pintype "passive"))
    )
    (net (code "57") (name "Net-(Q4-PadB)") (class "Default")
      (node (ref "Q4") (pin "B") (pinfunction "B_B") (pintype "passive"))
      (node (ref "R16") (pin "2") (pinfunction "2_2") (pintype "passive"))
    )
    (net (code "58") (name "Net-(Q5-PadB)") (class "Default")
      (node (ref "Q5") (pin "B") (pinfunction "B_B") (pintype "passive"))
      (node (ref "R15") (pin "2") (pinfunction "2_2") (pintype "passive"))
    )
    (net (code "59") (name "Net-(Q6-PadB)") (class "Default")
      (node (ref "Q6") (pin "B") (pinfunction "B_B") (pintype "passive"))
      (node (ref "R18") (pin "2") (pinfunction "2_2") (pintype "passive"))
    )
    (net (code "60") (name "Net-(U1-IO26)") (class "Default")
      (node (ref "TP1") (pin "TP") (pinfunction "TP_TP") (pintype "input"))
      (node (ref "U1") (pin "25") (pinfunction "IO26_25") (pintype "bidirectional"))
    )
    (net (code "61") (name "Net-(U4-OUT)") (class "Default")
      (node (ref "L2") (pin "1") (pinfunction "1_1") (pintype "passive"))
      (node (ref "U$8") (pin "OUT") (pinfunction "OUT_OUT") (pintype "bidirectional"))
      (node (ref "U4") (pin "2") (pinfunction "OUT_2") (pintype "output"))
    )
    (net (code "62") (name "Net-(U4-VIN)") (class "Default")
      (node (ref "C2") (pin "+") (pinfunction "+_+") (pintype "passive"))
      (node (ref "R19") (pin "1") (pinfunction "1_1") (pintype "passive"))
      (node (ref "U4") (pin "1") (pinfunction "VIN_1") (pintype "input"))
    )
    (net (code "63") (name "Net-(X1A-KL)") (class "Default")
      (node (ref "K1") (pin "NC") (pinfunction "NC_NC") (pintype "passive"))
      (node (ref "X1") (pin "1") (pinfunction "KL_1") (pintype "passive"))
    )
    (net (code "64") (name "Net-(X1B-KL)") (class "Default")
      (node (ref "K1") (pin "COM") (pinfunction "COM_COM") (pintype "passive"))
      (node (ref "X1") (pin "2") (pinfunction "KL_2") (pintype "passive"))
    )
    (net (code "65") (name "Net-(X1C-KL)") (class "Default")
      (node (ref "K1") (pin "NO") (pinfunction "NO_NO") (pintype "passive"))
      (node (ref "X1") (pin "3") (pinfunction "KL_3") (pintype "passive"))
    )
    (net (code "66") (name "Net-(X2A-KL)") (class "Default")
      (node (ref "K2") (pin "NC") (pinfunction "NC_NC") (pintype "passive"))
      (node (ref "X2") (pin "1") (pinfunction "KL_1") (pintype "passive"))
    )
    (net (code "67") (name "Net-(X2B-KL)") (class "Default")
      (node (ref "K2") (pin "COM") (pinfunction "COM_COM") (pintype "passive"))
      (node (ref "X2") (pin "2") (pinfunction "KL_2") (pintype "passive"))
    )
    (net (code "68") (name "Net-(X2C-KL)") (class "Default")
      (node (ref "K2") (pin "NO") (pinfunction "NO_NO") (pintype "passive"))
      (node (ref "X2") (pin "3") (pinfunction "KL_3") (pintype "passive"))
    )
    (net (code "69") (name "Net-(X3A-KL)") (class "Default")
      (node (ref "K3") (pin "NC") (pinfunction "NC_NC") (pintype "passive"))
      (node (ref "X3") (pin "1") (pinfunction "KL_1") (pintype "passive"))
    )
    (net (code "70") (name "Net-(X3B-KL)") (class "Default")
      (node (ref "K3") (pin "COM") (pinfunction "COM_COM") (pintype "passive"))
      (node (ref "X3") (pin "2") (pinfunction "KL_2") (pintype "passive"))
    )
    (net (code "71") (name "Net-(X3C-KL)") (class "Default")
      (node (ref "K3") (pin "NO") (pinfunction "NO_NO") (pintype "passive"))
      (node (ref "X3") (pin "3") (pinfunction "KL_3") (pintype "passive"))
    )
    (net (code "72") (name "Net-(X4A-KL)") (class "Default")
      (node (ref "K4") (pin "NC") (pinfunction "NC_NC") (pintype "passive"))
      (node (ref "X4") (pin "1") (pinfunction "KL_1") (pintype "passive"))
    )
    (net (code "73") (name "Net-(X4B-KL)") (class "Default")
      (node (ref "K4") (pin "COM") (pinfunction "COM_COM") (pintype "passive"))
      (node (ref "X4") (pin "2") (pinfunction "KL_2") (pintype "passive"))
    )
    (net (code "74") (name "Net-(X4C-KL)") (class "Default")
      (node (ref "K4") (pin "NO") (pinfunction "NO_NO") (pintype "passive"))
      (node (ref "X4") (pin "3") (pinfunction "KL_3") (pintype "passive"))
    )
    (net (code "75") (name "Net-(X5A-KL)") (class "Default")
      (node (ref "K5") (pin "NC") (pinfunction "NC_NC") (pintype "passive"))
      (node (ref "X5") (pin "1") (pinfunction "KL_1") (pintype "passive"))
    )
    (net (code "76") (name "Net-(X5B-KL)") (class "Default")
      (node (ref "K5") (pin "COM") (pinfunction "COM_COM") (pintype "passive"))
      (node (ref "X5") (pin "2") (pinfunction "KL_2") (pintype "passive"))
    )
    (net (code "77") (name "Net-(X5C-KL)") (class "Default")
      (node (ref "K5") (pin "NO") (pinfunction "NO_NO") (pintype "passive"))
      (node (ref "X5") (pin "3") (pinfunction "KL_3") (pintype "passive"))
    )
    (net (code "78") (name "Net-(X6A-KL)") (class "Default")
      (node (ref "K6") (pin "NC") (pinfunction "NC_NC") (pintype "passive"))
      (node (ref "X6") (pin "1") (pinfunction "KL_1") (pintype "passive"))
    )
    (net (code "79") (name "Net-(X6B-KL)") (class "Default")
      (node (ref "K6") (pin "COM") (pinfunction "COM_COM") (pintype "passive"))
      (node (ref "X6") (pin "2") (pinfunction "KL_2") (pintype "passive"))
    )
    (net (code "80") (name "Net-(X6C-KL)") (class "Default")
      (node (ref "K6") (pin "NO") (pinfunction "NO_NO") (pintype "passive"))
      (node (ref "X6") (pin "3") (pinfunction "KL_3") (pintype "passive"))
    )
    (net (code "81") (name "Net-(X7-ANT)") (class "Default")
      (node (ref "X7") (pin "P") (pinfunction "ANT_P") (pintype "bidirectional"))
      (node (ref "X8") (pin "3") (pinfunction "SIGNAL_3") (pintype "passive"))
    )
    (net (code "82") (name "RXD1") (class "Default")
      (node (ref "JP4") (pin "13") (pinfunction "13_13") (pintype "passive"))
      (node (ref "JP4") (pin "14") (pinfunction "14_14") (pintype "passive"))
      (node (ref "U1") (pin "37") (pinfunction "TXD0_37") (pintype "bidirectional"))
    )
    (net (code "83") (name "RXD2") (class "Default")
      (node (ref "JP5") (pin "1") (pinfunction "1_1") (pintype "passive"))
      (node (ref "JP5") (pin "2") (pinfunction "2_2") (pintype "passive"))
      (node (ref "U1") (pin "20") (pinfunction "IO17_20") (pintype "bidirectional"))
    )
    (net (code "84") (name "SCL") (class "Default")
      (node (ref "J3") (pin "RING2") (pinfunction "RING2_RING2") (pintype "bidirectional"))
      (node (ref "J4") (pin "RING2") (pinfunction "RING2_RING2") (pintype "bidirectional"))
      (node (ref "JP5") (pin "11") (pinfunction "11_11") (pintype "passive"))
      (node (ref "JP5") (pin "12") (pinfunction "12_12") (pintype "passive"))
      (node (ref "R1") (pin "2") (pinfunction "2_2") (pintype "passive"))
      (node (ref "U1") (pin "34") (pinfunction "IO40_34") (pintype "bidirectional"))
    )
    (net (code "85") (name "SDA") (class "Default")
      (node (ref "J3") (pin "RING1") (pinfunction "RING1_RING1") (pintype "bidirectional"))
      (node (ref "J4") (pin "RING1") (pinfunction "RING1_RING1") (pintype "bidirectional"))
      (node (ref "JP5") (pin "10") (pinfunction "10_10") (pintype "passive"))
      (node (ref "JP5") (pin "9") (pinfunction "9_9") (pintype "passive"))
      (node (ref "R2") (pin "2") (pinfunction "2_2") (pintype "passive"))
      (node (ref "U1") (pin "35") (pinfunction "IO41_35") (pintype "bidirectional"))
    )
    (net (code "86") (name "SHLD") (class "Default")
      (node (ref "CONN1") (pin "SHLD1") (pinfunction "SHLD_SHLD1") (pintype "bidirectional"))
      (node (ref "CONN1") (pin "SHLD2") (pinfunction "SHLD_SHLD2") (pintype "bidirectional"))
      (node (ref "CONN1") (pin "SHLD3") (pinfunction "SHLD_SHLD3") (pintype "bidirectional"))
      (node (ref "CONN1") (pin "SHLD4") (pinfunction "SHLD_SHLD4") (pintype "bidirectional"))
      (node (ref "CONN1") (pin "SHLD5") (pinfunction "SHLD_SHLD5") (pintype "bidirectional"))
      (node (ref "CONN1") (pin "SHLD6") (pinfunction "SHLD_SHLD6") (pintype "bidirectional"))
      (node (ref "CONN1") (pin "SHLD7") (pinfunction "SHLD_SHLD7") (pintype "bidirectional"))
      (node (ref "CONN1") (pin "SHLD8") (pinfunction "SHLD_SHLD8") (pintype "bidirectional"))
    )
    (net (code "87") (name "TXD1") (class "Default")
      (node (ref "JP4") (pin "11") (pinfunction "11_11") (pintype "passive"))
      (node (ref "JP4") (pin "12") (pinfunction "12_12") (pintype "passive"))
      (node (ref "U1") (pin "38") (pinfunction "RXD0_38") (pintype "bidirectional"))
    )
    (net (code "88") (name "TXD2") (class "Default")
      (node (ref "JP5") (pin "3") (pinfunction "3_3") (pintype "passive"))
      (node (ref "JP5") (pin "4") (pinfunction "4_4") (pintype "passive"))
      (node (ref "U1") (pin "21") (pinfunction "IO18_21") (pintype "bidirectional"))
    )
    (net (code "89") (name "VBUS") (class "Default")
      (node (ref "C1") (pin "1") (pinfunction "1_1") (pintype "passive"))
      (node (ref "D8") (pin "A") (pinfunction "A_A") (pintype "passive"))
      (node (ref "F2") (pin "2") (pinfunction "2_2") (pintype "passive"))
    )
    (net (code "90") (name "unconnected-(U$16-I3-Pad3)") (class "Default")
      (node (ref "U$16") (pin "3") (pinfunction "I3_3") (pintype "bidirectional"))
    )
    (net (code "91") (name "unconnected-(U$16-I4-Pad4)") (class "Default")
      (node (ref "U$16") (pin "4") (pinfunction "I4_4") (pintype "bidirectional"))
    )
    (net (code "92") (name "unconnected-(U$16-O3-Pad6)") (class "Default")
      (node (ref "U$16") (pin "6") (pinfunction "O3_6") (pintype "bidirectional"))
    )
    (net (code "93") (name "unconnected-(U$16-O4-Pad5)") (class "Default")
      (node (ref "U$16") (pin "5") (pinfunction "O4_5") (pintype "bidirectional"))
    )
    (net (code "94") (name "unconnected-(U1-IO1-Pad4)") (class "Default")
      (node (ref "U1") (pin "4") (pinfunction "IO1_4") (pintype "bidirectional"))
    )
    (net (code "95") (name "unconnected-(U1-IO3-Pad6)") (class "Default")
      (node (ref "U1") (pin "6") (pinfunction "IO3_6") (pintype "bidirectional"))
    )
    (net (code "96") (name "unconnected-(U1-IO4-Pad7)") (class "Default")
      (node (ref "U1") (pin "7") (pinfunction "IO4_7") (pintype "bidirectional"))
    )
    (net (code "97") (name "unconnected-(U1-IO5-Pad8)") (class "Default")
      (node (ref "U1") (pin "8") (pinfunction "IO5_8") (pintype "bidirectional"))
    )
    (net (code "98") (name "unconnected-(U1-IO6-Pad9)") (class "Default")
      (node (ref "U1") (pin "9") (pinfunction "IO6_9") (pintype "bidirectional"))
    )
    (net (code "99") (name "unconnected-(U1-IO7-Pad10)") (class "Default")
      (node (ref "U1") (pin "10") (pinfunction "IO7_10") (pintype "bidirectional"))
    )
    (net (code "100") (name "unconnected-(U1-IO8-Pad11)") (class "Default")
      (node (ref "U1") (pin "11") (pinfunction "IO8_11") (pintype "bidirectional"))
    )
    (net (code "101") (name "unconnected-(U1-IO9-Pad12)") (class "Default")
      (node (ref "U1") (pin "12") (pinfunction "IO9_12") (pintype "bidirectional"))
    )
    (net (code "102") (name "unconnected-(U1-IO14-Pad17)") (class "Default")
      (node (ref "U1") (pin "17") (pinfunction "IO14_17") (pintype "bidirectional"))
    )
    (net (code "103") (name "unconnected-(U1-IO42-Pad36)") (class "Default")
      (node (ref "U1") (pin "36") (pinfunction "IO42_36") (pintype "bidirectional"))
    )
    (net (code "104") (name "unconnected-(U1-IO45-Pad39)") (class "Default")
      (node (ref "U1") (pin "39") (pinfunction "IO45_39") (pintype "bidirectional"))
    )
    (net (code "105") (name "unconnected-(U1-IO46-Pad40)") (class "Default")
      (node (ref "U1") (pin "40") (pinfunction "IO46_40") (pintype "bidirectional"))
    )
  )
)
